# POG_PIN_Board.net
KiCad netlist of a schematic drawn in Altium Designer
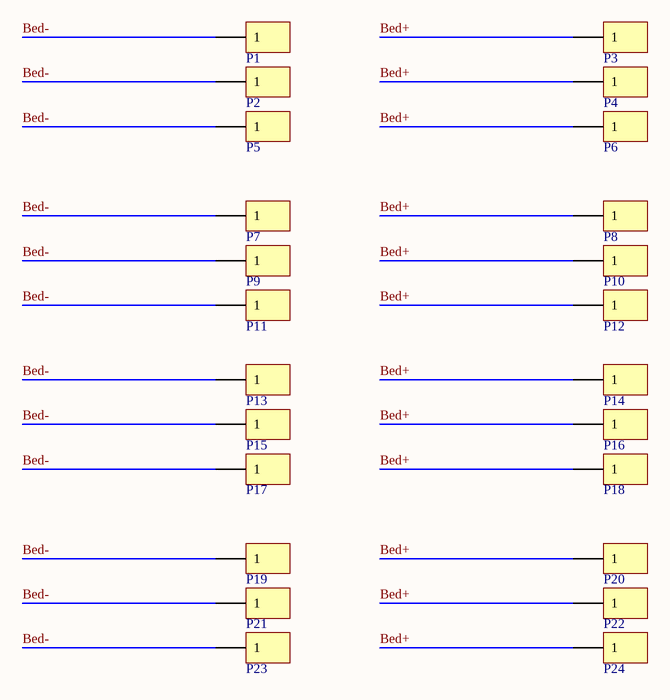
[diagram p0: POG_PIN_Board.SchDoc]

(export (version "E")
  (design (tool "Eeschema 10.0.6"))
  (components
    (comp (ref "P1")
      (value "CONN_X1")
      (footprint "SUN_Hole")
      (libsource (lib "POG_PIN_Board") (part "CONN_X1"))
    )
    (comp (ref "P2")
      (value "CONN_X1")
      (footprint "SUN_Hole")
      (libsource (lib "POG_PIN_Board") (part "CONN_X1"))
    )
    (comp (ref "P3")
      (value "CONN_X1")
      (footprint "SUN_Hole")
      (libsource (lib "POG_PIN_Board") (part "CONN_X1"))
    )
    (comp (ref "P4")
      (value "CONN_X1")
      (footprint "SUN_Hole")
      (libsource (lib "POG_PIN_Board") (part "CONN_X1"))
    )
    (comp (ref "P5")
      (value "CONN_X1")
      (footprint "SUN_Hole")
      (libsource (lib "POG_PIN_Board") (part "CONN_X1"))
    )
    (comp (ref "P6")
      (value "CONN_X1")
      (footprint "SUN_Hole")
      (libsource (lib "POG_PIN_Board") (part "CONN_X1"))
    )
    (comp (ref "P7")
      (value "CONN_X1")
      (footprint "SUN_Hole_medium")
      (libsource (lib "POG_PIN_Board") (part "CONN_X1"))
    )
    (comp (ref "P8")
      (value "CONN_X1")
      (footprint "SUN_Hole_medium")
      (libsource (lib "POG_PIN_Board") (part "CONN_X1"))
    )
    (comp (ref "P9")
      (value "CONN_X1")
      (footprint "SUN_Hole_medium")
      (libsource (lib "POG_PIN_Board") (part "CONN_X1"))
    )
    (comp (ref "P10")
      (value "CONN_X1")
      (footprint "SUN_Hole_medium")
      (libsource (lib "POG_PIN_Board") (part "CONN_X1"))
    )
    (comp (ref "P11")
      (value "CONN_X1")
      (footprint "SUN_Hole_medium")
      (libsource (lib "POG_PIN_Board") (part "CONN_X1"))
    )
    (comp (ref "P12")
      (value "CONN_X1")
      (footprint "SUN_Hole_medium")
      (libsource (lib "POG_PIN_Board") (part "CONN_X1"))
    )
    (comp (ref "P13")
      (value "CONN_X1")
      (footprint "SUN_Hole")
      (libsource (lib "POG_PIN_Board") (part "CONN_X1"))
    )
    (comp (ref "P14")
      (value "CONN_X1")
      (footprint "SUN_Hole")
      (libsource (lib "POG_PIN_Board") (part "CONN_X1"))
    )
    (comp (ref "P15")
      (value "CONN_X1")
      (footprint "SUN_Hole")
      (libsource (lib "POG_PIN_Board") (part "CONN_X1"))
    )
    (comp (ref "P16")
      (value "CONN_X1")
      (footprint "SUN_Hole")
      (libsource (lib "POG_PIN_Board") (part "CONN_X1"))
    )
    (comp (ref "P17")
      (value "CONN_X1")
      (footprint "SUN_Hole")
      (libsource (lib "POG_PIN_Board") (part "CONN_X1"))
    )
    (comp (ref "P18")
      (value "CONN_X1")
      (footprint "SUN_Hole")
      (libsource (lib "POG_PIN_Board") (part "CONN_X1"))
    )
    (comp (ref "P19")
      (value "CONN_X1")
      (footprint "SUN_Hole_medium")
      (libsource (lib "POG_PIN_Board") (part "CONN_X1"))
    )
    (comp (ref "P20")
      (value "CONN_X1")
      (footprint "SUN_Hole_medium")
      (libsource (lib "POG_PIN_Board") (part "CONN_X1"))
    )
    (comp (ref "P21")
      (value "CONN_X1")
      (footprint "SUN_Hole_medium")
      (libsource (lib "POG_PIN_Board") (part "CONN_X1"))
    )
    (comp (ref "P22")
      (value "CONN_X1")
      (footprint "SUN_Hole_medium")
      (libsource (lib "POG_PIN_Board") (part "CONN_X1"))
    )
    (comp (ref "P23")
      (value "CONN_X1")
      (footprint "SUN_Hole_medium")
      (libsource (lib "POG_PIN_Board") (part "CONN_X1"))
    )
    (comp (ref "P24")
      (value "CONN_X1")
      (footprint "SUN_Hole_medium")
      (libsource (lib "POG_PIN_Board") (part "CONN_X1"))
    )
  )
  (nets
    (net (code "1") (name "/Bed+") (class "Default")
      (node (ref "P10") (pin "1") (pinfunction "1_1") (pintype "passive"))
      (node (ref "P12") (pin "1") (pinfunction "1_1") (pintype "passive"))
      (node (ref "P14") (pin "1") (pinfunction "1_1") (pintype "passive"))
      (node (ref "P16") (pin "1") (pinfunction "1_1") (pintype "passive"))
      (node (ref "P18") (pin "1") (pinfunction "1_1") (pintype "passive"))
      (node (ref "P20") (pin "1") (pinfunction "1_1") (pintype "passive"))
      (node (ref "P22") (pin "1") (pinfunction "1_1") (pintype "passive"))
      (node (ref "P24") (pin "1") (pinfunction "1_1") (pintype "passive"))
      (node (ref "P3") (pin "1") (pinfunction "1_1") (pintype "passive"))
      (node (ref "P4") (pin "1") (pinfunction "1_1") (pintype "passive"))
      (node (ref "P6") (pin "1") (pinfunction "1_1") (pintype "passive"))
      (node (ref "P8") (pin "1") (pinfunction "1_1") (pintype "passive"))
    )
    (net (code "2") (name "/Bed-") (class "Default")
      (node (ref "P1") (pin "1") (pinfunction "1_1") (pintype "passive"))
      (node (ref "P11") (pin "1") (pinfunction "1_1") (pintype "passive"))
      (node (ref "P13") (pin "1") (pinfunction "1_1") (pintype "passive"))
      (node (ref "P15") (pin "1") (pinfunction "1_1") (pintype "passive"))
      (node (ref "P17") (pin "1") (pinfunction "1_1") (pintype "passive"))
      (node (ref "P19") (pin "1") (pinfunction "1_1") (pintype "passive"))
      (node (ref "P2") (pin "1") (pinfunction "1_1") (pintype "passive"))
      (node (ref "P21") (pin "1") (pinfunction "1_1") (pintype "passive"))
      (node (ref "P23") (pin "1") (pinfunction "1_1") (pintype "passive"))
      (node (ref "P5") (pin "1") (pinfunction "1_1") (pintype "passive"))
      (node (ref "P7") (pin "1") (pinfunction "1_1") (pintype "passive"))
      (node (ref "P9") (pin "1") (pinfunction "1_1") (pintype "passive"))
    )
  )
)
